# controller.net
KiCad netlist of a schematic drawn in EAGLE
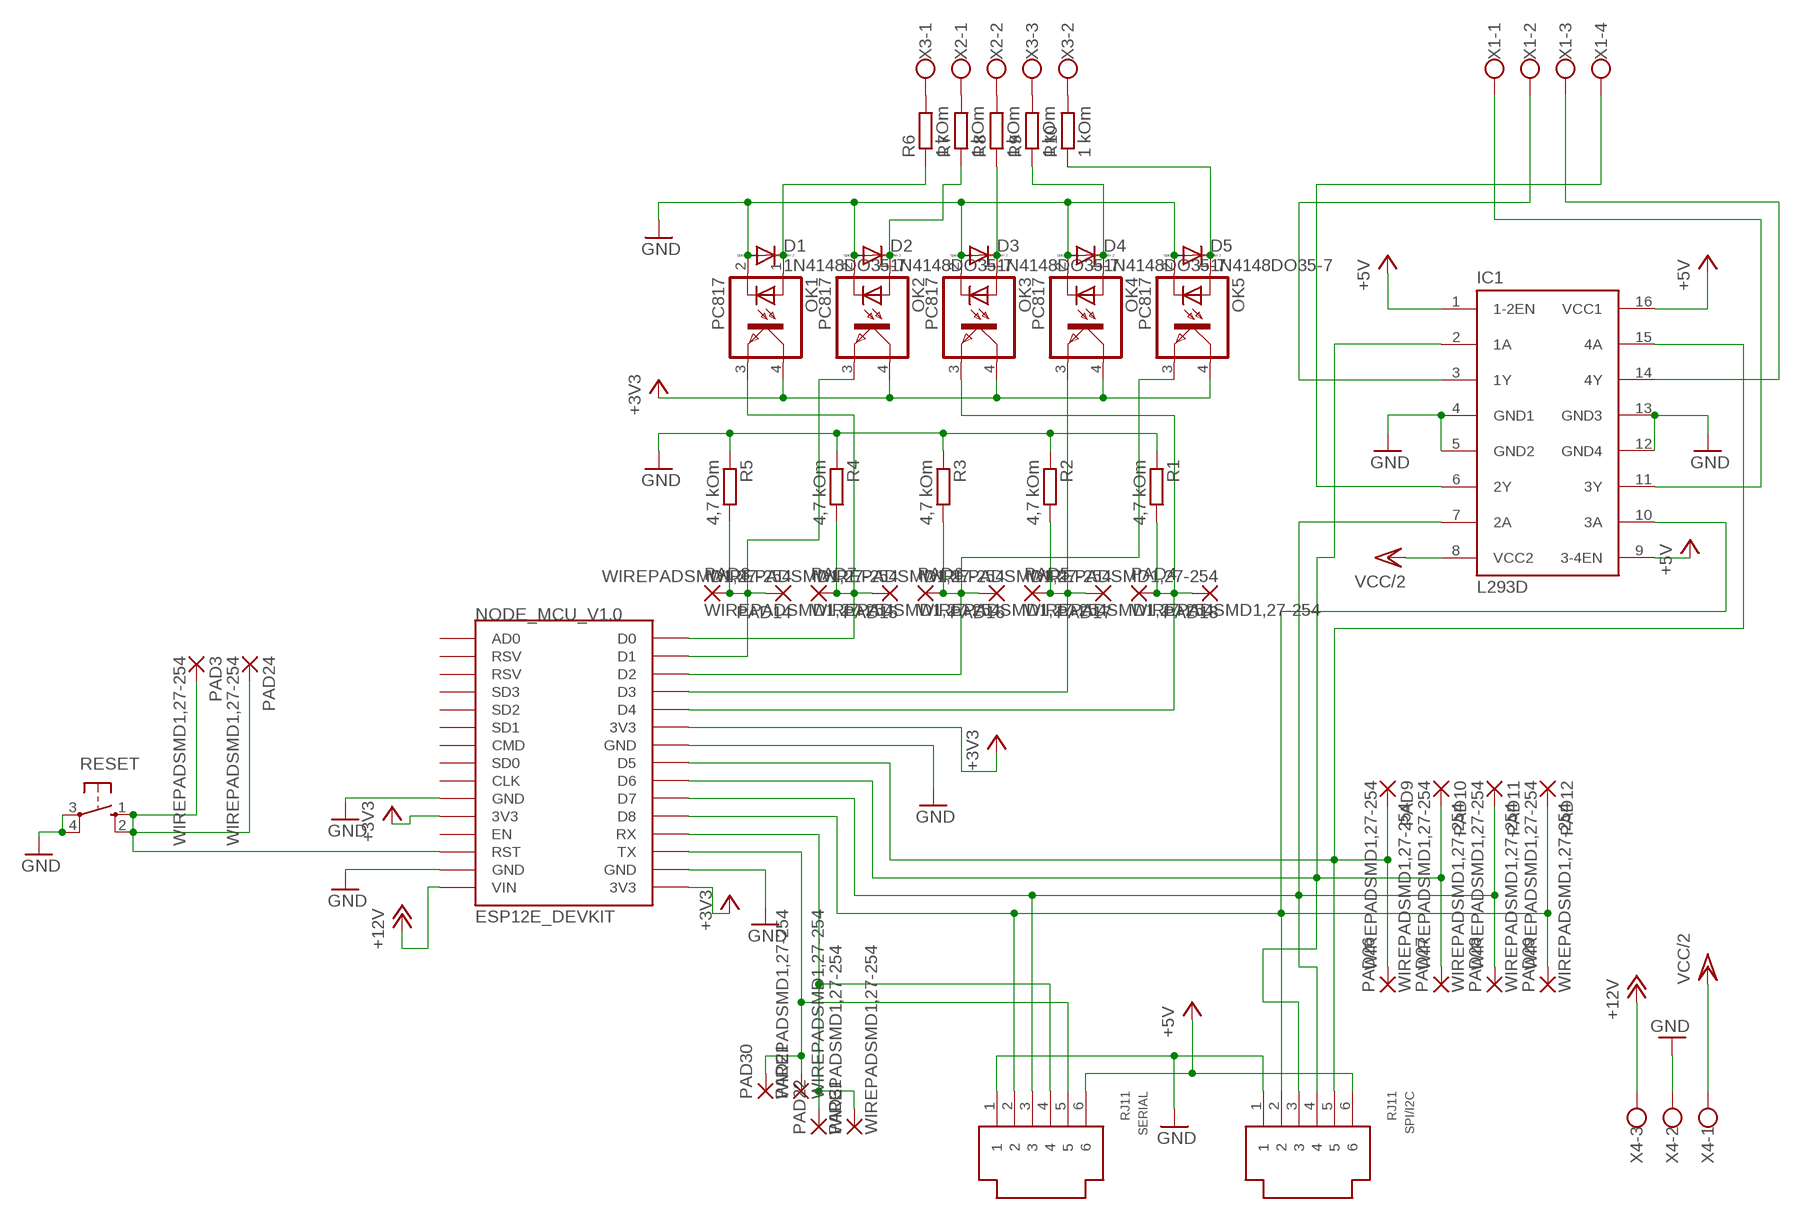
[diagram p0: schematic, sheet 1]
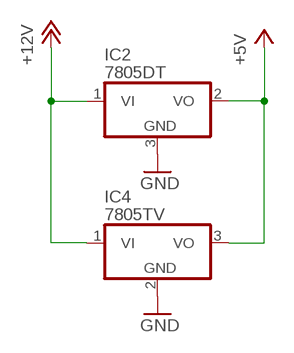
[diagram p1: schematic, sheet 2]
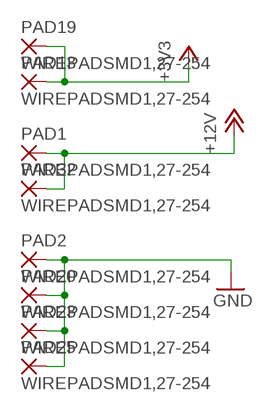
[diagram p2: schematic, sheet 3]
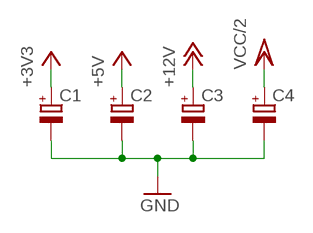
[diagram p3: schematic, sheet 4]

(export (version "E")
  (design (tool "Eeschema 10.0.6"))
  (components
    (comp (ref "PAD1")
      (value "WIREPADSMD1,27-254")
      (footprint "eagle-import:SMD1,27-2,54")
      (libsource (lib "eagle-import") (part "WIREPADSMD1,27-254"))
    )
    (comp (ref "PAD2")
      (value "WIREPADSMD1,27-254")
      (footprint "eagle-import:SMD1,27-2,54")
      (libsource (lib "eagle-import") (part "WIREPADSMD1,27-254"))
    )
    (comp (ref "PAD13")
      (value "WIREPADSMD1,27-254")
      (footprint "eagle-import:SMD1,27-2,54")
      (libsource (lib "eagle-import") (part "WIREPADSMD1,27-254"))
    )
    (comp (ref "PAD19")
      (value "WIREPADSMD1,27-254")
      (footprint "eagle-import:SMD1,27-2,54")
      (libsource (lib "eagle-import") (part "WIREPADSMD1,27-254"))
    )
    (comp (ref "PAD20")
      (value "WIREPADSMD1,27-254")
      (footprint "eagle-import:SMD1,27-2,54")
      (libsource (lib "eagle-import") (part "WIREPADSMD1,27-254"))
    )
    (comp (ref "PAD23")
      (value "WIREPADSMD1,27-254")
      (footprint "eagle-import:SMD1,27-2,54")
      (libsource (lib "eagle-import") (part "WIREPADSMD1,27-254"))
    )
    (comp (ref "PAD25")
      (value "WIREPADSMD1,27-254")
      (footprint "eagle-import:SMD1,27-2,54")
      (libsource (lib "eagle-import") (part "WIREPADSMD1,27-254"))
    )
    (comp (ref "PAD32")
      (value "WIREPADSMD1,27-254")
      (footprint "eagle-import:SMD1,27-2,54")
      (libsource (lib "eagle-import") (part "WIREPADSMD1,27-254"))
    )
    (comp (ref "C1")
      (value "CPOL-EUE2.5-5")
      (footprint "eagle-import:E2,5-5")
      (libsource (lib "eagle-import") (part "CPOL-EUE2.5-5"))
    )
    (comp (ref "C2")
      (value "CPOL-EUE2.5-5")
      (footprint "eagle-import:E2,5-5")
      (libsource (lib "eagle-import") (part "CPOL-EUE2.5-5"))
    )
    (comp (ref "C3")
      (value "CPOL-EUE2.5-5")
      (footprint "eagle-import:E2,5-5")
      (libsource (lib "eagle-import") (part "CPOL-EUE2.5-5"))
    )
    (comp (ref "C4")
      (value "CPOL-EUE2.5-5")
      (footprint "eagle-import:E2,5-5")
      (libsource (lib "eagle-import") (part "CPOL-EUE2.5-5"))
    )
    (comp (ref "D1")
      (value "1N4148DO35-7")
      (footprint "eagle-import:DO35-7")
      (libsource (lib "eagle-import") (part "1N4148DO35-7"))
    )
    (comp (ref "D2")
      (value "1N4148DO35-7")
      (footprint "eagle-import:DO35-7")
      (libsource (lib "eagle-import") (part "1N4148DO35-7"))
    )
    (comp (ref "D3")
      (value "1N4148DO35-7")
      (footprint "eagle-import:DO35-7")
      (libsource (lib "eagle-import") (part "1N4148DO35-7"))
    )
    (comp (ref "D4")
      (value "1N4148DO35-7")
      (footprint "eagle-import:DO35-7")
      (libsource (lib "eagle-import") (part "1N4148DO35-7"))
    )
    (comp (ref "D5")
      (value "1N4148DO35-7")
      (footprint "eagle-import:DO35-7")
      (libsource (lib "eagle-import") (part "1N4148DO35-7"))
    )
    (comp (ref "IC1")
      (value "L293D")
      (footprint "eagle-import:DIL16")
      (libsource (lib "eagle-import") (part "L293D"))
    )
    (comp (ref "NODE_MCU_V1.0")
      (value "ESP12E_DEVKIT")
      (footprint "eagle-import:ESP12E_DEVKIT")
      (libsource (lib "eagle-import") (part "ESP12E_DEVKIT"))
    )
    (comp (ref "OK1")
      (value "PC817")
      (footprint "eagle-import:DIL04")
      (fields (field (name "MPN") "PC817X4J000F"))
      (libsource (lib "eagle-import") (part "PC817"))
    )
    (comp (ref "OK2")
      (value "PC817")
      (footprint "eagle-import:DIL04")
      (fields (field (name "MPN") "PC817X4J000F"))
      (libsource (lib "eagle-import") (part "PC817"))
    )
    (comp (ref "OK3")
      (value "PC817")
      (footprint "eagle-import:DIL04")
      (fields (field (name "MPN") "PC817X4J000F"))
      (libsource (lib "eagle-import") (part "PC817"))
    )
    (comp (ref "OK4")
      (value "PC817")
      (footprint "eagle-import:DIL04")
      (fields (field (name "MPN") "PC817X4J000F"))
      (libsource (lib "eagle-import") (part "PC817"))
    )
    (comp (ref "OK5")
      (value "PC817")
      (footprint "eagle-import:DIL04")
      (fields (field (name "MPN") "PC817X4J000F"))
      (libsource (lib "eagle-import") (part "PC817"))
    )
    (comp (ref "PAD3")
      (value "WIREPADSMD1,27-254")
      (footprint "eagle-import:SMD1,27-2,54")
      (libsource (lib "eagle-import") (part "WIREPADSMD1,27-254"))
    )
    (comp (ref "PAD4")
      (value "WIREPADSMD1,27-254")
      (footprint "eagle-import:SMD1,27-2,54")
      (libsource (lib "eagle-import") (part "WIREPADSMD1,27-254"))
    )
    (comp (ref "PAD5")
      (value "WIREPADSMD1,27-254")
      (footprint "eagle-import:SMD1,27-2,54")
      (libsource (lib "eagle-import") (part "WIREPADSMD1,27-254"))
    )
    (comp (ref "PAD6")
      (value "WIREPADSMD1,27-254")
      (footprint "eagle-import:SMD1,27-2,54")
      (libsource (lib "eagle-import") (part "WIREPADSMD1,27-254"))
    )
    (comp (ref "PAD7")
      (value "WIREPADSMD1,27-254")
      (footprint "eagle-import:SMD1,27-2,54")
      (libsource (lib "eagle-import") (part "WIREPADSMD1,27-254"))
    )
    (comp (ref "PAD8")
      (value "WIREPADSMD1,27-254")
      (footprint "eagle-import:SMD1,27-2,54")
      (libsource (lib "eagle-import") (part "WIREPADSMD1,27-254"))
    )
    (comp (ref "PAD9")
      (value "WIREPADSMD1,27-254")
      (footprint "eagle-import:SMD1,27-2,54")
      (libsource (lib "eagle-import") (part "WIREPADSMD1,27-254"))
    )
    (comp (ref "PAD10")
      (value "WIREPADSMD1,27-254")
      (footprint "eagle-import:SMD1,27-2,54")
      (libsource (lib "eagle-import") (part "WIREPADSMD1,27-254"))
    )
    (comp (ref "PAD11")
      (value "WIREPADSMD1,27-254")
      (footprint "eagle-import:SMD1,27-2,54")
      (libsource (lib "eagle-import") (part "WIREPADSMD1,27-254"))
    )
    (comp (ref "PAD12")
      (value "WIREPADSMD1,27-254")
      (footprint "eagle-import:SMD1,27-2,54")
      (libsource (lib "eagle-import") (part "WIREPADSMD1,27-254"))
    )
    (comp (ref "PAD14")
      (value "WIREPADSMD1,27-254")
      (footprint "eagle-import:SMD1,27-2,54")
      (libsource (lib "eagle-import") (part "WIREPADSMD1,27-254"))
    )
    (comp (ref "PAD15")
      (value "WIREPADSMD1,27-254")
      (footprint "eagle-import:SMD1,27-2,54")
      (libsource (lib "eagle-import") (part "WIREPADSMD1,27-254"))
    )
    (comp (ref "PAD16")
      (value "WIREPADSMD1,27-254")
      (footprint "eagle-import:SMD1,27-2,54")
      (libsource (lib "eagle-import") (part "WIREPADSMD1,27-254"))
    )
    (comp (ref "PAD17")
      (value "WIREPADSMD1,27-254")
      (footprint "eagle-import:SMD1,27-2,54")
      (libsource (lib "eagle-import") (part "WIREPADSMD1,27-254"))
    )
    (comp (ref "PAD18")
      (value "WIREPADSMD1,27-254")
      (footprint "eagle-import:SMD1,27-2,54")
      (libsource (lib "eagle-import") (part "WIREPADSMD1,27-254"))
    )
    (comp (ref "PAD21")
      (value "WIREPADSMD1,27-254")
      (footprint "eagle-import:SMD1,27-2,54")
      (libsource (lib "eagle-import") (part "WIREPADSMD1,27-254"))
    )
    (comp (ref "PAD22")
      (value "WIREPADSMD1,27-254")
      (footprint "eagle-import:SMD1,27-2,54")
      (libsource (lib "eagle-import") (part "WIREPADSMD1,27-254"))
    )
    (comp (ref "PAD24")
      (value "WIREPADSMD1,27-254")
      (footprint "eagle-import:SMD1,27-2,54")
      (libsource (lib "eagle-import") (part "WIREPADSMD1,27-254"))
    )
    (comp (ref "PAD26")
      (value "WIREPADSMD1,27-254")
      (footprint "eagle-import:SMD1,27-2,54")
      (libsource (lib "eagle-import") (part "WIREPADSMD1,27-254"))
    )
    (comp (ref "PAD27")
      (value "WIREPADSMD1,27-254")
      (footprint "eagle-import:SMD1,27-2,54")
      (libsource (lib "eagle-import") (part "WIREPADSMD1,27-254"))
    )
    (comp (ref "PAD28")
      (value "WIREPADSMD1,27-254")
      (footprint "eagle-import:SMD1,27-2,54")
      (libsource (lib "eagle-import") (part "WIREPADSMD1,27-254"))
    )
    (comp (ref "PAD29")
      (value "WIREPADSMD1,27-254")
      (footprint "eagle-import:SMD1,27-2,54")
      (libsource (lib "eagle-import") (part "WIREPADSMD1,27-254"))
    )
    (comp (ref "PAD30")
      (value "WIREPADSMD1,27-254")
      (footprint "eagle-import:SMD1,27-2,54")
      (libsource (lib "eagle-import") (part "WIREPADSMD1,27-254"))
    )
    (comp (ref "PAD31")
      (value "WIREPADSMD1,27-254")
      (footprint "eagle-import:SMD1,27-2,54")
      (libsource (lib "eagle-import") (part "WIREPADSMD1,27-254"))
    )
    (comp (ref "R1")
      (value "4,7 kOm")
      (footprint "eagle-import:0204_5")
      (libsource (lib "eagle-import") (part "R-EU_0204/5"))
    )
    (comp (ref "R2")
      (value "4,7 kOm")
      (footprint "eagle-import:0204_5")
      (libsource (lib "eagle-import") (part "R-EU_0204/5"))
    )
    (comp (ref "R3")
      (value "4,7 kOm")
      (footprint "eagle-import:0204_5")
      (libsource (lib "eagle-import") (part "R-EU_0204/5"))
    )
    (comp (ref "R4")
      (value "4,7 kOm")
      (footprint "eagle-import:0204_5")
      (libsource (lib "eagle-import") (part "R-EU_0204/5"))
    )
    (comp (ref "R5")
      (value "4,7 kOm")
      (footprint "eagle-import:0204_5")
      (libsource (lib "eagle-import") (part "R-EU_0204/5"))
    )
    (comp (ref "R6")
      (value "1 kOm")
      (footprint "eagle-import:0204V")
      (libsource (lib "eagle-import") (part "R-EU_0204/2V"))
    )
    (comp (ref "R7")
      (value "1 kOm")
      (footprint "eagle-import:0204V")
      (libsource (lib "eagle-import") (part "R-EU_0204/2V"))
    )
    (comp (ref "R8")
      (value "1 kOm")
      (footprint "eagle-import:0204V")
      (libsource (lib "eagle-import") (part "R-EU_0204/2V"))
    )
    (comp (ref "R9")
      (value "1 kOm")
      (footprint "eagle-import:0204V")
      (libsource (lib "eagle-import") (part "R-EU_0204/2V"))
    )
    (comp (ref "R10")
      (value "1 kOm")
      (footprint "eagle-import:0204V")
      (libsource (lib "eagle-import") (part "R-EU_0204/2V"))
    )
    (comp (ref "RESET")
      (value "10-XX")
      (footprint "eagle-import:B3F-10XX")
      (fields (field (name "MPN") "B3F-1000"))
      (libsource (lib "eagle-import") (part "10-XX"))
    )
    (comp (ref "SERIAL")
      (value "RJ11")
      (footprint "eagle-import:RJ11")
      (libsource (lib "eagle-import") (part "RJ11"))
    )
    (comp (ref "SPI/I2C")
      (value "RJ11")
      (footprint "eagle-import:RJ11")
      (libsource (lib "eagle-import") (part "RJ11"))
    )
    (comp (ref "X1")
      (value "W237-4")
      (footprint "eagle-import:W237-4")
      (libsource (lib "eagle-import") (part "W237-4"))
    )
    (comp (ref "X2")
      (value "W237-102")
      (footprint "eagle-import:W237-102")
      (fields (field (name "MPN") "237-102"))
      (libsource (lib "eagle-import") (part "W237-102"))
    )
    (comp (ref "X3")
      (value "W237-103")
      (footprint "eagle-import:W237-103")
      (fields (field (name "MPN") "237-103"))
      (libsource (lib "eagle-import") (part "W237-103"))
    )
    (comp (ref "X4")
      (value "W237-103")
      (footprint "eagle-import:W237-103")
      (fields (field (name "MPN") "237-103"))
      (libsource (lib "eagle-import") (part "W237-103"))
    )
    (comp (ref "IC2")
      (value "7805DT")
      (footprint "eagle-import:TO252")
      (libsource (lib "eagle-import") (part "linear4_78DT05"))
    )
    (comp (ref "IC4")
      (value "7805TV")
      (footprint "eagle-import:TO220V")
      (libsource (lib "eagle-import") (part "78TV05"))
    )
  )
  (nets
    (net (code "1") (name "+3V3") (class "Default")
      (node (ref "C1") (pin "+") (pinfunction "+_+") (pintype "passive"))
      (node (ref "NODE_MCU_V1.0") (pin "3V3@0") (pinfunction "3V3_3V3@0") (pintype "bidirectional"))
      (node (ref "NODE_MCU_V1.0") (pin "3V3@1") (pinfunction "3V3_3V3@1") (pintype "bidirectional"))
      (node (ref "NODE_MCU_V1.0") (pin "3V3@2") (pinfunction "3V3_3V3@2") (pintype "bidirectional"))
      (node (ref "OK1") (pin "4") (pinfunction "COL_4") (pintype "passive"))
      (node (ref "OK2") (pin "4") (pinfunction "COL_4") (pintype "passive"))
      (node (ref "OK3") (pin "4") (pinfunction "COL_4") (pintype "passive"))
      (node (ref "OK4") (pin "4") (pinfunction "COL_4") (pintype "passive"))
      (node (ref "OK5") (pin "4") (pinfunction "COL_4") (pintype "passive"))
      (node (ref "PAD13") (pin "1") (pinfunction "P_1") (pintype "passive"))
      (node (ref "PAD19") (pin "1") (pinfunction "P_1") (pintype "passive"))
    )
    (net (code "2") (name "+5V") (class "Default")
      (node (ref "C2") (pin "+") (pinfunction "+_+") (pintype "passive"))
      (node (ref "IC1") (pin "1") (pinfunction "1-2EN_1") (pintype "input"))
      (node (ref "IC1") (pin "16") (pinfunction "VCC1_16") (pintype "power_in"))
      (node (ref "IC1") (pin "9") (pinfunction "3-4EN_9") (pintype "input"))
      (node (ref "IC2") (pin "2") (pinfunction "VO_2") (pintype "passive"))
      (node (ref "IC4") (pin "3") (pinfunction "VO_3") (pintype "passive"))
      (node (ref "SERIAL") (pin "6") (pinfunction "6_6") (pintype "bidirectional"))
      (node (ref "SPI/I2C") (pin "6") (pinfunction "6_6") (pintype "bidirectional"))
    )
    (net (code "3") (name "+12V") (class "Default")
      (node (ref "C3") (pin "+") (pinfunction "+_+") (pintype "passive"))
      (node (ref "IC2") (pin "1") (pinfunction "VI_1") (pintype "input"))
      (node (ref "IC4") (pin "1") (pinfunction "VI_1") (pintype "input"))
      (node (ref "NODE_MCU_V1.0") (pin "VIN") (pinfunction "VIN_VIN") (pintype "bidirectional"))
      (node (ref "PAD1") (pin "1") (pinfunction "P_1") (pintype "passive"))
      (node (ref "PAD32") (pin "1") (pinfunction "P_1") (pintype "passive"))
      (node (ref "X4") (pin "3") (pinfunction "KL_3") (pintype "passive"))
    )
    (net (code "4") (name "GND") (class "Default")
      (node (ref "C1") (pin "-") (pinfunction "-_-") (pintype "passive"))
      (node (ref "C2") (pin "-") (pinfunction "-_-") (pintype "passive"))
      (node (ref "C3") (pin "-") (pinfunction "-_-") (pintype "passive"))
      (node (ref "C4") (pin "-") (pinfunction "-_-") (pintype "passive"))
      (node (ref "D1") (pin "A") (pinfunction "A_A") (pintype "passive"))
      (node (ref "D2") (pin "A") (pinfunction "A_A") (pintype "passive"))
      (node (ref "D3") (pin "A") (pinfunction "A_A") (pintype "passive"))
      (node (ref "D4") (pin "A") (pinfunction "A_A") (pintype "passive"))
      (node (ref "D5") (pin "A") (pinfunction "A_A") (pintype "passive"))
      (node (ref "IC1") (pin "12") (pinfunction "GND4_12") (pintype "power_in"))
      (node (ref "IC1") (pin "13") (pinfunction "GND3_13") (pintype "power_in"))
      (node (ref "IC1") (pin "4") (pinfunction "GND1_4") (pintype "power_in"))
      (node (ref "IC1") (pin "5") (pinfunction "GND2_5") (pintype "power_in"))
      (node (ref "IC2") (pin "3") (pinfunction "GND_3") (pintype "passive"))
      (node (ref "IC4") (pin "2") (pinfunction "GND_2") (pintype "passive"))
      (node (ref "NODE_MCU_V1.0") (pin "GND@0") (pinfunction "GND_GND@0") (pintype "bidirectional"))
      (node (ref "NODE_MCU_V1.0") (pin "GND@1") (pinfunction "GND_GND@1") (pintype "bidirectional"))
      (node (ref "NODE_MCU_V1.0") (pin "GND@2") (pinfunction "GND_GND@2") (pintype "bidirectional"))
      (node (ref "NODE_MCU_V1.0") (pin "GND@3") (pinfunction "GND_GND@3") (pintype "bidirectional"))
      (node (ref "OK1") (pin "2") (pinfunction "C_2") (pintype "passive"))
      (node (ref "OK2") (pin "2") (pinfunction "C_2") (pintype "passive"))
      (node (ref "OK3") (pin "2") (pinfunction "C_2") (pintype "passive"))
      (node (ref "OK4") (pin "2") (pinfunction "C_2") (pintype "passive"))
      (node (ref "OK5") (pin "2") (pinfunction "C_2") (pintype "passive"))
      (node (ref "PAD2") (pin "1") (pinfunction "P_1") (pintype "passive"))
      (node (ref "PAD20") (pin "1") (pinfunction "P_1") (pintype "passive"))
      (node (ref "PAD23") (pin "1") (pinfunction "P_1") (pintype "passive"))
      (node (ref "PAD25") (pin "1") (pinfunction "P_1") (pintype "passive"))
      (node (ref "R1") (pin "1") (pinfunction "1_1") (pintype "passive"))
      (node (ref "R2") (pin "1") (pinfunction "1_1") (pintype "passive"))
      (node (ref "R3") (pin "1") (pinfunction "1_1") (pintype "passive"))
      (node (ref "R4") (pin "1") (pinfunction "1_1") (pintype "passive"))
      (node (ref "R5") (pin "1") (pinfunction "1_1") (pintype "passive"))
      (node (ref "RESET") (pin "3") (pinfunction "P_3") (pintype "passive"))
      (node (ref "RESET") (pin "4") (pinfunction "P1_4") (pintype "passive"))
      (node (ref "SERIAL") (pin "1") (pinfunction "1_1") (pintype "bidirectional"))
      (node (ref "SPI/I2C") (pin "1") (pinfunction "1_1") (pintype "bidirectional"))
      (node (ref "X4") (pin "2") (pinfunction "KL_2") (pintype "passive"))
    )
    (net (code "5") (name "Net-(IC1-1A)") (class "Default")
      (node (ref "IC1") (pin "2") (pinfunction "1A_2") (pintype "input"))
      (node (ref "NODE_MCU_V1.0") (pin "D6") (pinfunction "D6_D6") (pintype "bidirectional"))
      (node (ref "PAD10") (pin "1") (pinfunction "P_1") (pintype "passive"))
      (node (ref "PAD27") (pin "1") (pinfunction "P_1") (pintype "passive"))
      (node (ref "SPI/I2C") (pin "3") (pinfunction "3_3") (pintype "bidirectional"))
    )
    (net (code "6") (name "Net-(IC1-1Y)") (class "Default")
      (node (ref "IC1") (pin "3") (pinfunction "1Y_3") (pintype "output"))
      (node (ref "X1") (pin "2") (pinfunction "KL_2") (pintype "passive"))
    )
    (net (code "7") (name "Net-(IC1-2A)") (class "Default")
      (node (ref "IC1") (pin "7") (pinfunction "2A_7") (pintype "input"))
      (node (ref "NODE_MCU_V1.0") (pin "D7") (pinfunction "D7_D7") (pintype "bidirectional"))
      (node (ref "PAD11") (pin "1") (pinfunction "P_1") (pintype "passive"))
      (node (ref "PAD28") (pin "1") (pinfunction "P_1") (pintype "passive"))
      (node (ref "SERIAL") (pin "3") (pinfunction "3_3") (pintype "bidirectional"))
      (node (ref "SPI/I2C") (pin "4") (pinfunction "4_4") (pintype "bidirectional"))
    )
    (net (code "8") (name "Net-(IC1-2Y)") (class "Default")
      (node (ref "IC1") (pin "6") (pinfunction "2Y_6") (pintype "output"))
      (node (ref "X1") (pin "4") (pinfunction "KL_4") (pintype "passive"))
    )
    (net (code "9") (name "Net-(IC1-3A)") (class "Default")
      (node (ref "IC1") (pin "10") (pinfunction "3A_10") (pintype "input"))
      (node (ref "NODE_MCU_V1.0") (pin "D8") (pinfunction "D8_D8") (pintype "bidirectional"))
      (node (ref "PAD12") (pin "1") (pinfunction "P_1") (pintype "passive"))
      (node (ref "PAD29") (pin "1") (pinfunction "P_1") (pintype "passive"))
      (node (ref "SERIAL") (pin "2") (pinfunction "2_2") (pintype "bidirectional"))
      (node (ref "SPI/I2C") (pin "2") (pinfunction "2_2") (pintype "bidirectional"))
    )
    (net (code "10") (name "Net-(IC1-3Y)") (class "Default")
      (node (ref "IC1") (pin "11") (pinfunction "3Y_11") (pintype "output"))
      (node (ref "X1") (pin "1") (pinfunction "KL_1") (pintype "passive"))
    )
    (net (code "11") (name "Net-(IC1-4A)") (class "Default")
      (node (ref "IC1") (pin "15") (pinfunction "4A_15") (pintype "input"))
      (node (ref "NODE_MCU_V1.0") (pin "D5") (pinfunction "D5_D5") (pintype "bidirectional"))
      (node (ref "PAD26") (pin "1") (pinfunction "P_1") (pintype "passive"))
      (node (ref "PAD9") (pin "1") (pinfunction "P_1") (pintype "passive"))
      (node (ref "SPI/I2C") (pin "5") (pinfunction "5_5") (pintype "bidirectional"))
    )
    (net (code "12") (name "Net-(IC1-4Y)") (class "Default")
      (node (ref "IC1") (pin "14") (pinfunction "4Y_14") (pintype "output"))
      (node (ref "X1") (pin "3") (pinfunction "KL_3") (pintype "passive"))
    )
    (net (code "13") (name "Net-(OK1-A)") (class "Default")
      (node (ref "D1") (pin "C") (pinfunction "C_C") (pintype "passive"))
      (node (ref "OK1") (pin "1") (pinfunction "A_1") (pintype "passive"))
      (node (ref "R6") (pin "1") (pinfunction "1_1") (pintype "passive"))
    )
    (net (code "14") (name "Net-(OK1-EMIT)") (class "Default")
      (node (ref "NODE_MCU_V1.0") (pin "D0") (pinfunction "D0_D0") (pintype "bidirectional"))
      (node (ref "OK1") (pin "3") (pinfunction "EMIT_3") (pintype "passive"))
      (node (ref "PAD15") (pin "1") (pinfunction "P_1") (pintype "passive"))
      (node (ref "PAD7") (pin "1") (pinfunction "P_1") (pintype "passive"))
      (node (ref "R4") (pin "2") (pinfunction "2_2") (pintype "passive"))
    )
    (net (code "15") (name "Net-(OK2-A)") (class "Default")
      (node (ref "D2") (pin "C") (pinfunction "C_C") (pintype "passive"))
      (node (ref "OK2") (pin "1") (pinfunction "A_1") (pintype "passive"))
      (node (ref "R7") (pin "1") (pinfunction "1_1") (pintype "passive"))
    )
    (net (code "16") (name "Net-(OK2-EMIT)") (class "Default")
      (node (ref "NODE_MCU_V1.0") (pin "D1") (pinfunction "D1_D1") (pintype "bidirectional"))
      (node (ref "OK2") (pin "3") (pinfunction "EMIT_3") (pintype "passive"))
      (node (ref "PAD14") (pin "1") (pinfunction "P_1") (pintype "passive"))
      (node (ref "PAD8") (pin "1") (pinfunction "P_1") (pintype "passive"))
      (node (ref "R5") (pin "2") (pinfunction "2_2") (pintype "passive"))
    )
    (net (code "17") (name "Net-(OK3-A)") (class "Default")
      (node (ref "D3") (pin "C") (pinfunction "C_C") (pintype "passive"))
      (node (ref "OK3") (pin "1") (pinfunction "A_1") (pintype "passive"))
      (node (ref "R8") (pin "1") (pinfunction "1_1") (pintype "passive"))
    )
    (net (code "18") (name "Net-(OK3-EMIT)") (class "Default")
      (node (ref "NODE_MCU_V1.0") (pin "D4") (pinfunction "D4_D4") (pintype "bidirectional"))
      (node (ref "OK3") (pin "3") (pinfunction "EMIT_3") (pintype "passive"))
      (node (ref "PAD18") (pin "1") (pinfunction "P_1") (pintype "passive"))
      (node (ref "PAD4") (pin "1") (pinfunction "P_1") (pintype "passive"))
      (node (ref "R1") (pin "2") (pinfunction "2_2") (pintype "passive"))
    )
    (net (code "19") (name "Net-(OK4-A)") (class "Default")
      (node (ref "D4") (pin "C") (pinfunction "C_C") (pintype "passive"))
      (node (ref "OK4") (pin "1") (pinfunction "A_1") (pintype "passive"))
      (node (ref "R9") (pin "1") (pinfunction "1_1") (pintype "passive"))
    )
    (net (code "20") (name "Net-(OK4-EMIT)") (class "Default")
      (node (ref "NODE_MCU_V1.0") (pin "D3") (pinfunction "D3_D3") (pintype "bidirectional"))
      (node (ref "OK4") (pin "3") (pinfunction "EMIT_3") (pintype "passive"))
      (node (ref "PAD17") (pin "1") (pinfunction "P_1") (pintype "passive"))
      (node (ref "PAD5") (pin "1") (pinfunction "P_1") (pintype "passive"))
      (node (ref "R2") (pin "2") (pinfunction "2_2") (pintype "passive"))
    )
    (net (code "21") (name "Net-(OK5-A)") (class "Default")
      (node (ref "D5") (pin "C") (pinfunction "C_C") (pintype "passive"))
      (node (ref "OK5") (pin "1") (pinfunction "A_1") (pintype "passive"))
      (node (ref "R10") (pin "1") (pinfunction "1_1") (pintype "passive"))
    )
    (net (code "22") (name "Net-(OK5-EMIT)") (class "Default")
      (node (ref "NODE_MCU_V1.0") (pin "D2") (pinfunction "D2_D2") (pintype "bidirectional"))
      (node (ref "OK5") (pin "3") (pinfunction "EMIT_3") (pintype "passive"))
      (node (ref "PAD16") (pin "1") (pinfunction "P_1") (pintype "passive"))
      (node (ref "PAD6") (pin "1") (pinfunction "P_1") (pintype "passive"))
      (node (ref "R3") (pin "2") (pinfunction "2_2") (pintype "passive"))
    )
    (net (code "23") (name "Net-(PAD21-P)") (class "Default")
      (node (ref "NODE_MCU_V1.0") (pin "TX") (pinfunction "TX_TX") (pintype "bidirectional"))
      (node (ref "PAD21") (pin "1") (pinfunction "P_1") (pintype "passive"))
      (node (ref "PAD30") (pin "1") (pinfunction "P_1") (pintype "passive"))
      (node (ref "SERIAL") (pin "5") (pinfunction "5_5") (pintype "bidirectional"))
    )
    (net (code "24") (name "Net-(PAD22-P)") (class "Default")
      (node (ref "NODE_MCU_V1.0") (pin "RX") (pinfunction "RX_RX") (pintype "bidirectional"))
      (node (ref "PAD22") (pin "1") (pinfunction "P_1") (pintype "passive"))
      (node (ref "PAD31") (pin "1") (pinfunction "P_1") (pintype "passive"))
      (node (ref "SERIAL") (pin "4") (pinfunction "4_4") (pintype "bidirectional"))
    )
    (net (code "25") (name "Net-(PAD24-P)") (class "Default")
      (node (ref "NODE_MCU_V1.0") (pin "RST") (pinfunction "RST_RST") (pintype "bidirectional"))
      (node (ref "PAD24") (pin "1") (pinfunction "P_1") (pintype "passive"))
      (node (ref "PAD3") (pin "1") (pinfunction "P_1") (pintype "passive"))
      (node (ref "RESET") (pin "1") (pinfunction "S_1") (pintype "passive"))
      (node (ref "RESET") (pin "2") (pinfunction "S1_2") (pintype "passive"))
    )
    (net (code "26") (name "Net-(X2A-KL)") (class "Default")
      (node (ref "R7") (pin "2") (pinfunction "2_2") (pintype "passive"))
      (node (ref "X2") (pin "1") (pinfunction "KL_1") (pintype "passive"))
    )
    (net (code "27") (name "Net-(X2B-KL)") (class "Default")
      (node (ref "R8") (pin "2") (pinfunction "2_2") (pintype "passive"))
      (node (ref "X2") (pin "2") (pinfunction "KL_2") (pintype "passive"))
    )
    (net (code "28") (name "Net-(X3A-KL)") (class "Default")
      (node (ref "R6") (pin "2") (pinfunction "2_2") (pintype "passive"))
      (node (ref "X3") (pin "1") (pinfunction "KL_1") (pintype "passive"))
    )
    (net (code "29") (name "Net-(X3B-KL)") (class "Default")
      (node (ref "R10") (pin "2") (pinfunction "2_2") (pintype "passive"))
      (node (ref "X3") (pin "2") (pinfunction "KL_2") (pintype "passive"))
    )
    (net (code "30") (name "Net-(X3C-KL)") (class "Default")
      (node (ref "R9") (pin "2") (pinfunction "2_2") (pintype "passive"))
      (node (ref "X3") (pin "3") (pinfunction "KL_3") (pintype "passive"))
    )
    (net (code "31") (name "VCC{slash}2") (class "Default")
      (node (ref "C4") (pin "+") (pinfunction "+_+") (pintype "passive"))
      (node (ref "IC1") (pin "8") (pinfunction "VCC2_8") (pintype "power_in"))
      (node (ref "X4") (pin "1") (pinfunction "KL_1") (pintype "passive"))
    )
    (net (code "32") (name "unconnected-(NODE_MCU_V1.0-PadAD0)") (class "Default")
      (node (ref "NODE_MCU_V1.0") (pin "AD0") (pinfunction "AD0_AD0") (pintype "bidirectional"))
    )
    (net (code "33") (name "unconnected-(NODE_MCU_V1.0-PadCLK)") (class "Default")
      (node (ref "NODE_MCU_V1.0") (pin "CLK") (pinfunction "CLK_CLK") (pintype "bidirectional"))
    )
    (net (code "34") (name "unconnected-(NODE_MCU_V1.0-PadCMD)") (class "Default")
      (node (ref "NODE_MCU_V1.0") (pin "CMD") (pinfunction "CMD_CMD") (pintype "bidirectional"))
    )
    (net (code "35") (name "unconnected-(NODE_MCU_V1.0-PadEN)") (class "Default")
      (node (ref "NODE_MCU_V1.0") (pin "EN") (pinfunction "EN_EN") (pintype "bidirectional"))
    )
    (net (code "36") (name "unconnected-(NODE_MCU_V1.0-PadSD0)") (class "Default")
      (node (ref "NODE_MCU_V1.0") (pin "SD0") (pinfunction "SD0_SD0") (pintype "bidirectional"))
    )
    (net (code "37") (name "unconnected-(NODE_MCU_V1.0-PadSD1)") (class "Default")
      (node (ref "NODE_MCU_V1.0") (pin "SD1") (pinfunction "SD1_SD1") (pintype "bidirectional"))
    )
    (net (code "38") (name "unconnected-(NODE_MCU_V1.0-PadSD2)") (class "Default")
      (node (ref "NODE_MCU_V1.0") (pin "SD2") (pinfunction "SD2_SD2") (pintype "bidirectional"))
    )
    (net (code "39") (name "unconnected-(NODE_MCU_V1.0-PadSD3)") (class "Default")
      (node (ref "NODE_MCU_V1.0") (pin "SD3") (pinfunction "SD3_SD3") (pintype "bidirectional"))
    )
    (net (code "40") (name "unconnected-(NODE_MCU_V1.0-RSV-PadRSV@0)") (class "Default")
      (node (ref "NODE_MCU_V1.0") (pin "RSV@0") (pinfunction "RSV_RSV@0") (pintype "bidirectional"))
    )
    (net (code "41") (name "unconnected-(NODE_MCU_V1.0-RSV-PadRSV@1)") (class "Default")
      (node (ref "NODE_MCU_V1.0") (pin "RSV@1") (pinfunction "RSV_RSV@1") (pintype "bidirectional"))
    )
  )
)
